# RHD2000_cable_adapt2.net
KiCad netlist of a schematic drawn in EAGLE
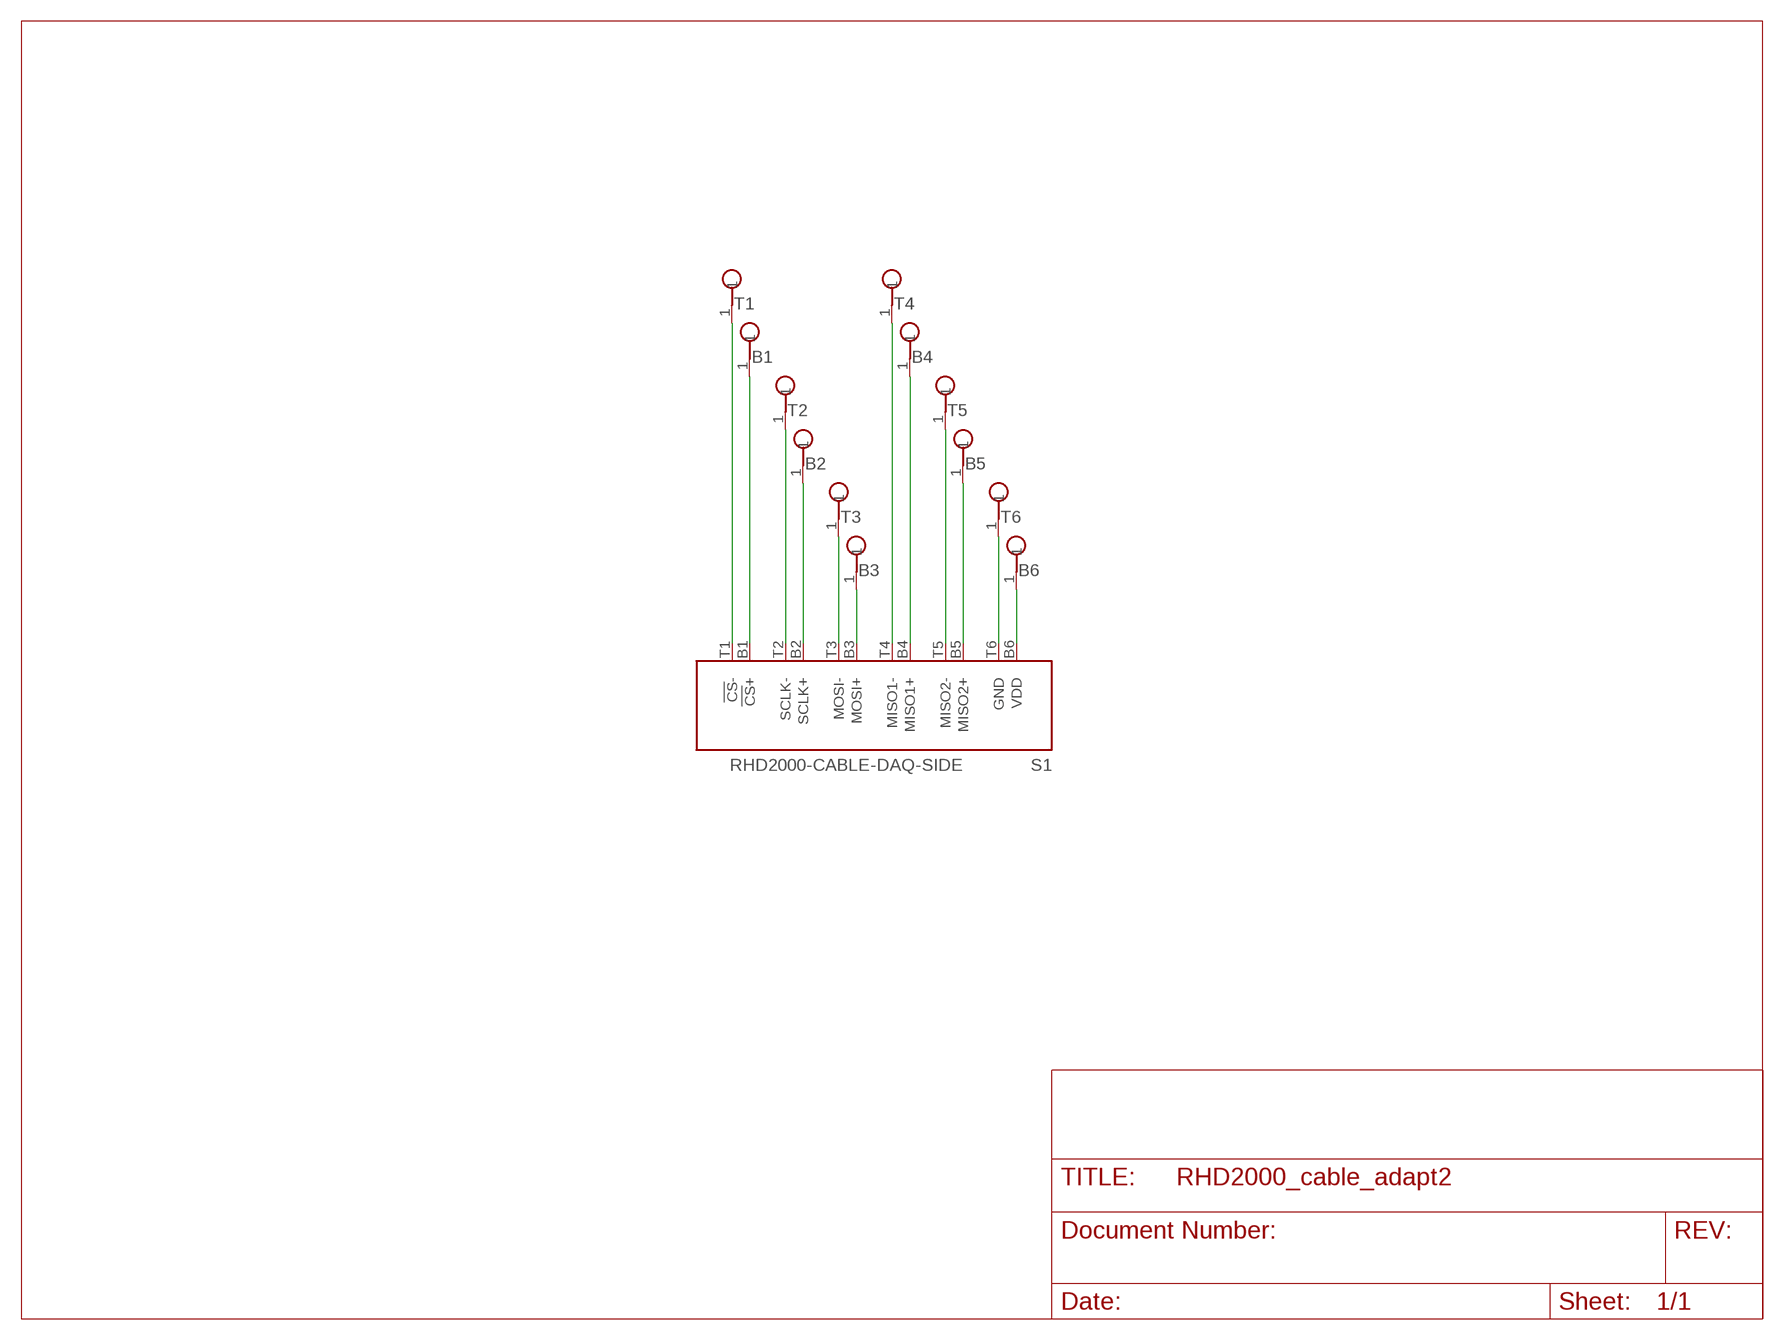
[diagram p0: schematic, sheet 1]

(export (version "E")
  (design (tool "Eeschema 10.0.6"))
  (components
    (comp (ref "B1")
      (value "TESTPOINT")
      (footprint "eagle-import:TESTPOINT")
      (libsource (lib "eagle-import") (part "TESTPOINT"))
    )
    (comp (ref "B2")
      (value "TESTPOINT")
      (footprint "eagle-import:TESTPOINT")
      (libsource (lib "eagle-import") (part "TESTPOINT"))
    )
    (comp (ref "B3")
      (value "TESTPOINT")
      (footprint "eagle-import:TESTPOINT")
      (libsource (lib "eagle-import") (part "TESTPOINT"))
    )
    (comp (ref "B4")
      (value "TESTPOINT")
      (footprint "eagle-import:TESTPOINT")
      (libsource (lib "eagle-import") (part "TESTPOINT"))
    )
    (comp (ref "B5")
      (value "TESTPOINT")
      (footprint "eagle-import:TESTPOINT")
      (libsource (lib "eagle-import") (part "TESTPOINT"))
    )
    (comp (ref "B6")
      (value "TESTPOINT")
      (footprint "eagle-import:TESTPOINT")
      (libsource (lib "eagle-import") (part "TESTPOINT"))
    )
    (comp (ref "S1")
      (value "RHD2000-CABLE-DAQ-SIDE")
      (footprint "eagle-import:OMNETICS_PZN-12-AA")
      (libsource (lib "eagle-import") (part "RHD2000-CABLE-DAQ-SIDE"))
    )
    (comp (ref "T1")
      (value "TESTPOINT")
      (footprint "eagle-import:TESTPOINT")
      (libsource (lib "eagle-import") (part "TESTPOINT"))
    )
    (comp (ref "T2")
      (value "TESTPOINT")
      (footprint "eagle-import:TESTPOINT")
      (libsource (lib "eagle-import") (part "TESTPOINT"))
    )
    (comp (ref "T3")
      (value "TESTPOINT")
      (footprint "eagle-import:TESTPOINT")
      (libsource (lib "eagle-import") (part "TESTPOINT"))
    )
    (comp (ref "T4")
      (value "TESTPOINT")
      (footprint "eagle-import:TESTPOINT")
      (libsource (lib "eagle-import") (part "TESTPOINT"))
    )
    (comp (ref "T5")
      (value "TESTPOINT")
      (footprint "eagle-import:TESTPOINT")
      (libsource (lib "eagle-import") (part "TESTPOINT"))
    )
    (comp (ref "T6")
      (value "TESTPOINT")
      (footprint "eagle-import:TESTPOINT")
      (libsource (lib "eagle-import") (part "TESTPOINT"))
    )
  )
  (nets
    (net (code "1") (name "Net-(S1-GND)") (class "Default")
      (node (ref "S1") (pin "T6") (pinfunction "GND_T6") (pintype "power_in"))
      (node (ref "T6") (pin "1") (pinfunction "1_1") (pintype "passive"))
    )
    (net (code "2") (name "Net-(S1-MISO1+)") (class "Default")
      (node (ref "B4") (pin "1") (pinfunction "1_1") (pintype "passive"))
      (node (ref "S1") (pin "B4") (pinfunction "MISO1+_B4") (pintype "bidirectional"))
    )
    (net (code "3") (name "Net-(S1-MISO1-)") (class "Default")
      (node (ref "S1") (pin "T4") (pinfunction "MISO1-_T4") (pintype "bidirectional"))
      (node (ref "T4") (pin "1") (pinfunction "1_1") (pintype "passive"))
    )
    (net (code "4") (name "Net-(S1-MISO2+)") (class "Default")
      (node (ref "B5") (pin "1") (pinfunction "1_1") (pintype "passive"))
      (node (ref "S1") (pin "B5") (pinfunction "MISO2+_B5") (pintype "bidirectional"))
    )
    (net (code "5") (name "Net-(S1-MISO2-)") (class "Default")
      (node (ref "S1") (pin "T5") (pinfunction "MISO2-_T5") (pintype "bidirectional"))
      (node (ref "T5") (pin "1") (pinfunction "1_1") (pintype "passive"))
    )
    (net (code "6") (name "Net-(S1-MOSI+)") (class "Default")
      (node (ref "B3") (pin "1") (pinfunction "1_1") (pintype "passive"))
      (node (ref "S1") (pin "B3") (pinfunction "MOSI+_B3") (pintype "bidirectional"))
    )
    (net (code "7") (name "Net-(S1-MOSI-)") (class "Default")
      (node (ref "S1") (pin "T3") (pinfunction "MOSI-_T3") (pintype "bidirectional"))
      (node (ref "T3") (pin "1") (pinfunction "1_1") (pintype "passive"))
    )
    (net (code "8") (name "Net-(S1-SCLK+)") (class "Default")
      (node (ref "B2") (pin "1") (pinfunction "1_1") (pintype "passive"))
      (node (ref "S1") (pin "B2") (pinfunction "SCLK+_B2") (pintype "bidirectional"))
    )
    (net (code "9") (name "Net-(S1-SCLK-)") (class "Default")
      (node (ref "S1") (pin "T2") (pinfunction "SCLK-_T2") (pintype "bidirectional"))
      (node (ref "T2") (pin "1") (pinfunction "1_1") (pintype "passive"))
    )
    (net (code "10") (name "Net-(S1-VDD)") (class "Default")
      (node (ref "B6") (pin "1") (pinfunction "1_1") (pintype "passive"))
      (node (ref "S1") (pin "B6") (pinfunction "VDD_B6") (pintype "bidirectional"))
    )
    (net (code "11") (name "Net-(S1-~{CS}+)") (class "Default")
      (node (ref "B1") (pin "1") (pinfunction "1_1") (pintype "passive"))
      (node (ref "S1") (pin "B1") (pinfunction "~{CS}+_B1") (pintype "bidirectional"))
    )
    (net (code "12") (name "Net-(S1-~{CS}-)") (class "Default")
      (node (ref "S1") (pin "T1") (pinfunction "~{CS}-_T1") (pintype "bidirectional"))
      (node (ref "T1") (pin "1") (pinfunction "1_1") (pintype "passive"))
    )
  )
)
